# ibmpc.net
KiCad netlist of a schematic drawn in EAGLE
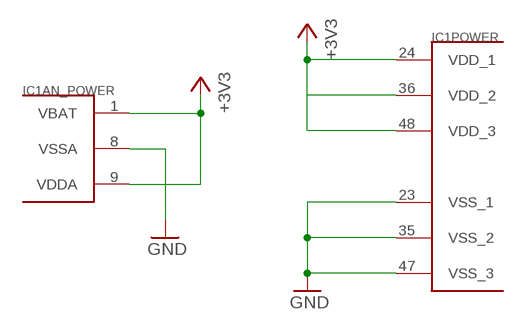
[diagram p0: schematic, sheet 1, part 1 of 2]
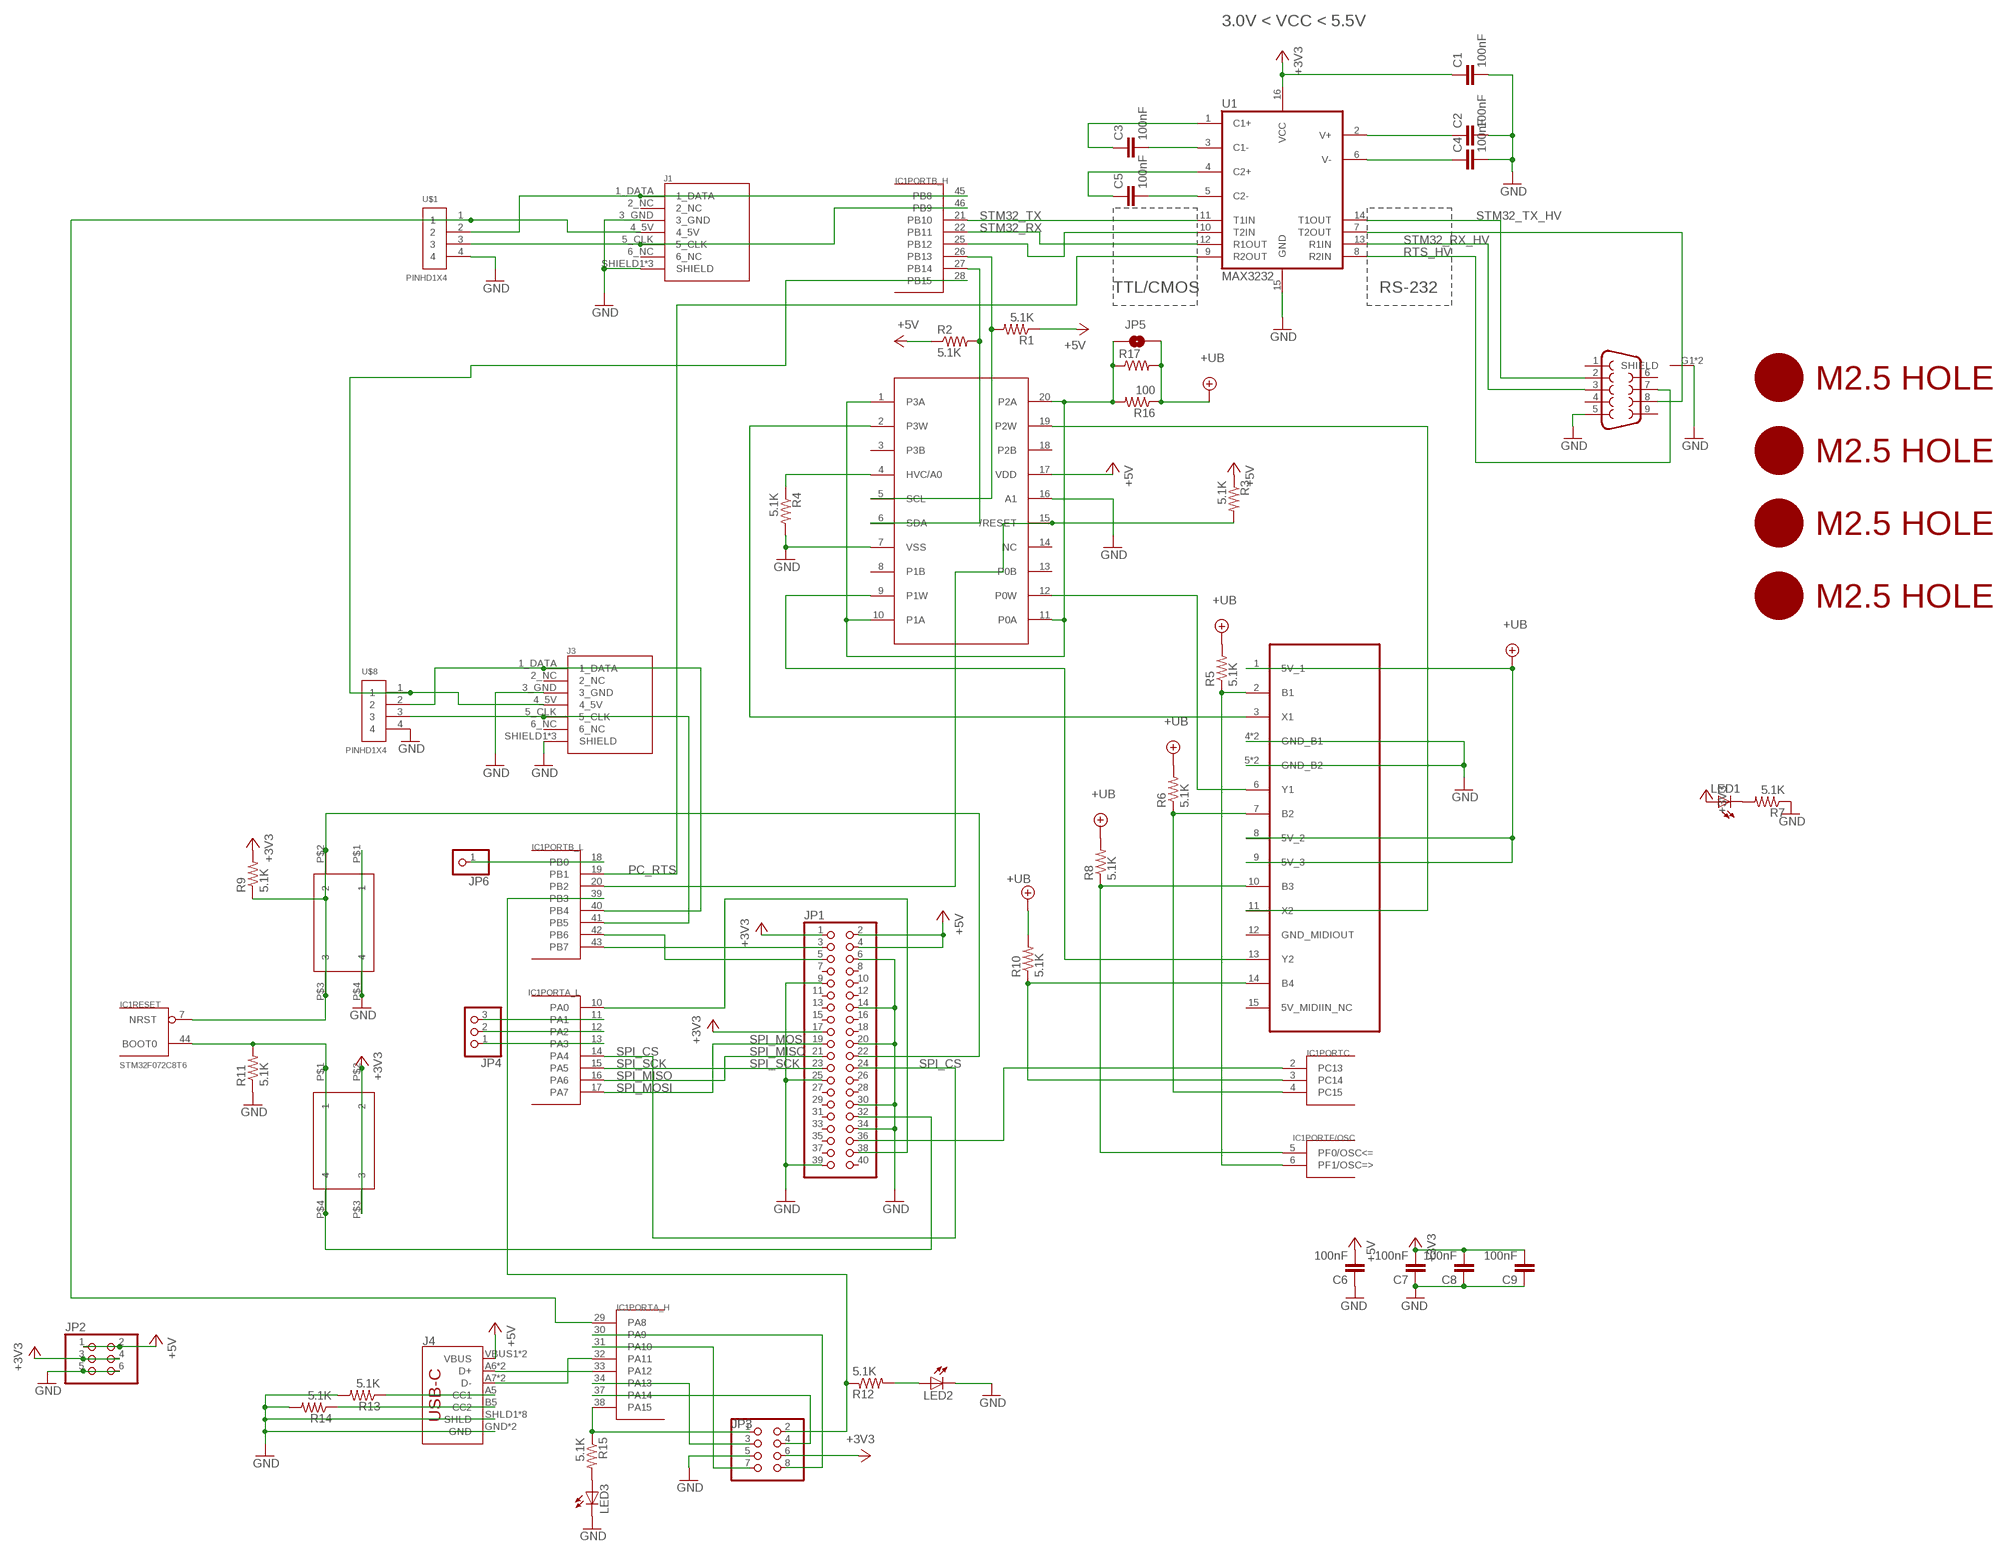
[diagram p1: schematic, sheet 1, part 2 of 2]

(export (version "E")
  (design (tool "Eeschema 10.0.6"))
  (components
    (comp (ref "C1")
      (value "100nF")
      (footprint "eagle-import:0805@1")
      (libsource (lib "eagle-import") (part "CAP0805"))
    )
    (comp (ref "C2")
      (value "100nF")
      (footprint "eagle-import:0805@1")
      (libsource (lib "eagle-import") (part "CAP0805"))
    )
    (comp (ref "C3")
      (value "100nF")
      (footprint "eagle-import:0805@1")
      (libsource (lib "eagle-import") (part "CAP0805"))
    )
    (comp (ref "C4")
      (value "100nF")
      (footprint "eagle-import:0805@1")
      (libsource (lib "eagle-import") (part "CAP0805"))
    )
    (comp (ref "C5")
      (value "100nF")
      (footprint "eagle-import:0805@1")
      (libsource (lib "eagle-import") (part "CAP0805"))
    )
    (comp (ref "C6")
      (value "100nF")
      (footprint "eagle-import:0805@1")
      (libsource (lib "eagle-import") (part "CAP0805"))
    )
    (comp (ref "C7")
      (value "100nF")
      (footprint "eagle-import:0805@1")
      (libsource (lib "eagle-import") (part "CAP0805"))
    )
    (comp (ref "C8")
      (value "100nF")
      (footprint "eagle-import:0805@1")
      (libsource (lib "eagle-import") (part "CAP0805"))
    )
    (comp (ref "C9")
      (value "100nF")
      (footprint "eagle-import:0805@1")
      (libsource (lib "eagle-import") (part "CAP0805"))
    )
    (comp (ref "IC1")
      (value "STM32F072C8T6")
      (footprint "eagle-import:TQFP48")
      (libsource (lib "eagle-import") (part "STM32F072C8T6"))
    )
    (comp (ref "J1")
      (value "DIN7")
      (footprint "eagle-import:DIN7")
      (libsource (lib "eagle-import") (part "DIN7"))
    )
    (comp (ref "J2")
      (value "DB9MALE")
      (footprint "eagle-import:DB9_MALE")
      (libsource (lib "eagle-import") (part "DB9MALE"))
    )
    (comp (ref "J3")
      (value "DIN7")
      (footprint "eagle-import:DIN7")
      (libsource (lib "eagle-import") (part "DIN7"))
    )
    (comp (ref "J4")
      (value "USB_C16PIN")
      (footprint "eagle-import:USB-C-16P")
      (libsource (lib "eagle-import") (part "USB_C16PIN"))
    )
    (comp (ref "JP1")
      (value "PINHD-2X20-BIG")
      (footprint "eagle-import:2X20-BIG")
      (libsource (lib "eagle-import") (part "PINHD-2X20-BIG"))
    )
    (comp (ref "JP2")
      (value "PINHD-2X3")
      (footprint "eagle-import:2X03")
      (libsource (lib "eagle-import") (part "PINHD-2X3"))
    )
    (comp (ref "JP3")
      (value "PINHD-2X4")
      (footprint "eagle-import:2X04")
      (libsource (lib "eagle-import") (part "PINHD-2X4"))
    )
    (comp (ref "JP4")
      (value "PINHD-1X3CB")
      (footprint "eagle-import:1X03-CLEANBIG")
      (libsource (lib "eagle-import") (part "PINHD-1X3CB"))
    )
    (comp (ref "JP5")
      (value "JUMPER-SMT_2_NO_NO-SILK")
      (footprint "eagle-import:SMT-JUMPER_2_NO_NO-SILK")
      (libsource (lib "eagle-import") (part "JUMPER-SMT_2_NO_NO-SILK"))
    )
    (comp (ref "JP6")
      (value "PINHD-1X1CB")
      (footprint "eagle-import:1X01-CLEANBIG")
      (libsource (lib "eagle-import") (part "PINHD-1X1CB"))
    )
    (comp (ref "LED1")
      (value "LEDCHIP-LED0805")
      (footprint "eagle-import:CHIP-LED0805")
      (libsource (lib "eagle-import") (part "LEDCHIP-LED0805"))
    )
    (comp (ref "LED2")
      (value "LEDCHIP-LED0805")
      (footprint "eagle-import:CHIP-LED0805")
      (libsource (lib "eagle-import") (part "LEDCHIP-LED0805"))
    )
    (comp (ref "LED3")
      (value "LEDCHIP-LED0805")
      (footprint "eagle-import:CHIP-LED0805")
      (libsource (lib "eagle-import") (part "LEDCHIP-LED0805"))
    )
    (comp (ref "R1")
      (value "5.1K")
      (footprint "eagle-import:0805")
      (libsource (lib "eagle-import") (part "RESISTOR0805-RES"))
    )
    (comp (ref "R2")
      (value "5.1K")
      (footprint "eagle-import:0805")
      (libsource (lib "eagle-import") (part "RESISTOR0805-RES"))
    )
    (comp (ref "R3")
      (value "5.1K")
      (footprint "eagle-import:0805")
      (libsource (lib "eagle-import") (part "RESISTOR0805-RES"))
    )
    (comp (ref "R4")
      (value "5.1K")
      (footprint "eagle-import:0805")
      (libsource (lib "eagle-import") (part "RESISTOR0805-RES"))
    )
    (comp (ref "R5")
      (value "5.1K")
      (footprint "eagle-import:0805")
      (libsource (lib "eagle-import") (part "RESISTOR0805-RES"))
    )
    (comp (ref "R6")
      (value "5.1K")
      (footprint "eagle-import:0805")
      (libsource (lib "eagle-import") (part "RESISTOR0805-RES"))
    )
    (comp (ref "R7")
      (value "5.1K")
      (footprint "eagle-import:0805")
      (libsource (lib "eagle-import") (part "RESISTOR0805-RES"))
    )
    (comp (ref "R8")
      (value "5.1K")
      (footprint "eagle-import:0805")
      (libsource (lib "eagle-import") (part "RESISTOR0805-RES"))
    )
    (comp (ref "R9")
      (value "5.1K")
      (footprint "eagle-import:0805")
      (libsource (lib "eagle-import") (part "RESISTOR0805-RES"))
    )
    (comp (ref "R10")
      (value "5.1K")
      (footprint "eagle-import:0805")
      (libsource (lib "eagle-import") (part "RESISTOR0805-RES"))
    )
    (comp (ref "R11")
      (value "5.1K")
      (footprint "eagle-import:0805")
      (libsource (lib "eagle-import") (part "RESISTOR0805-RES"))
    )
    (comp (ref "R12")
      (value "5.1K")
      (footprint "eagle-import:0805")
      (libsource (lib "eagle-import") (part "RESISTOR0805-RES"))
    )
    (comp (ref "R13")
      (value "5.1K")
      (footprint "eagle-import:0805")
      (libsource (lib "eagle-import") (part "RESISTOR0805-RES"))
    )
    (comp (ref "R14")
      (value "5.1K")
      (footprint "eagle-import:0805")
      (libsource (lib "eagle-import") (part "RESISTOR0805-RES"))
    )
    (comp (ref "R15")
      (value "5.1K")
      (footprint "eagle-import:0805")
      (libsource (lib "eagle-import") (part "RESISTOR0805-RES"))
    )
    (comp (ref "R16")
      (value "100")
      (footprint "eagle-import:0805")
      (libsource (lib "eagle-import") (part "RESISTOR0805-RES"))
    )
    (comp (ref "R17")
      (value "R-US_0204/7")
      (footprint "eagle-import:0204_7")
      (libsource (lib "eagle-import") (part "R-US_0204/7"))
    )
    (comp (ref "SW1")
      (value "324_SW")
      (footprint "eagle-import:342_SWICH_FOOT")
      (libsource (lib "eagle-import") (part "324_SW"))
    )
    (comp (ref "SW2")
      (value "324_SW")
      (footprint "eagle-import:342_SWICH_FOOT")
      (libsource (lib "eagle-import") (part "324_SW"))
    )
    (comp (ref "U$1")
      (value "PINHD1X4")
      (footprint "eagle-import:1X04-CLEANBIG")
      (libsource (lib "eagle-import") (part "PINHD1X4"))
    )
    (comp (ref "U$2")
      (value "M2.5HOLE")
      (footprint "eagle-import:M2.5HOLE")
      (libsource (lib "eagle-import") (part "M2.5HOLE"))
    )
    (comp (ref "U$3")
      (value "M2.5HOLE")
      (footprint "eagle-import:M2.5HOLE")
      (libsource (lib "eagle-import") (part "M2.5HOLE"))
    )
    (comp (ref "U$5")
      (value "MCP4451")
      (footprint "eagle-import:TSSOP20")
      (libsource (lib "eagle-import") (part "MCP4451"))
    )
    (comp (ref "U$6")
      (value "M2.5HOLE")
      (footprint "eagle-import:M2.5HOLE")
      (libsource (lib "eagle-import") (part "M2.5HOLE"))
    )
    (comp (ref "U$7")
      (value "M2.5HOLE")
      (footprint "eagle-import:M2.5HOLE")
      (libsource (lib "eagle-import") (part "M2.5HOLE"))
    )
    (comp (ref "U$8")
      (value "PINHD1X4")
      (footprint "eagle-import:1X04-CLEANBIG")
      (libsource (lib "eagle-import") (part "PINHD1X4"))
    )
    (comp (ref "U$9")
      (value "GAMEPORT_15P")
      (footprint "eagle-import:DA15")
      (libsource (lib "eagle-import") (part "GAMEPORT_15P"))
    )
    (comp (ref "U1")
      (value "MAX3232")
      (footprint "eagle-import:SO016")
      (libsource (lib "eagle-import") (part "MAX232SOIC16"))
    )
  )
  (nets
    (net (code "1") (name "+3V3") (class "Default")
      (node (ref "C1") (pin "1") (pinfunction "1_1") (pintype "passive"))
      (node (ref "C7") (pin "2") (pinfunction "2_2") (pintype "passive"))
      (node (ref "C8") (pin "2") (pinfunction "2_2") (pintype "passive"))
      (node (ref "C9") (pin "2") (pinfunction "2_2") (pintype "passive"))
      (node (ref "IC1") (pin "1") (pinfunction "VBAT_1") (pintype "power_in"))
      (node (ref "IC1") (pin "24") (pinfunction "VDD_1_24") (pintype "power_in"))
      (node (ref "IC1") (pin "36") (pinfunction "VDD_2_36") (pintype "power_in"))
      (node (ref "IC1") (pin "48") (pinfunction "VDD_3_48") (pintype "power_in"))
      (node (ref "IC1") (pin "9") (pinfunction "VDDA_9") (pintype "power_in"))
      (node (ref "JP1") (pin "1") (pinfunction "1_1") (pintype "passive"))
      (node (ref "JP1") (pin "17") (pinfunction "17_17") (pintype "passive"))
      (node (ref "JP2") (pin "3") (pinfunction "3_3") (pintype "passive"))
      (node (ref "JP2") (pin "4") (pinfunction "4_4") (pintype "passive"))
      (node (ref "JP3") (pin "6") (pinfunction "6_6") (pintype "passive"))
      (node (ref "LED1") (pin "A") (pinfunction "A_A") (pintype "passive"))
      (node (ref "R9") (pin "2") (pinfunction "2_2") (pintype "passive"))
      (node (ref "SW2") (pin "P$2") (pinfunction "2_P$2") (pintype "bidirectional"))
      (node (ref "SW2") (pin "P$3") (pinfunction "3_P$3") (pintype "bidirectional"))
      (node (ref "U1") (pin "16") (pinfunction "VCC_16") (pintype "bidirectional"))
    )
    (net (code "2") (name "+5V") (class "Default")
      (node (ref "C6") (pin "2") (pinfunction "2_2") (pintype "passive"))
      (node (ref "J4") (pin "VBUS1") (pinfunction "VBUS_VBUS1") (pintype "bidirectional"))
      (node (ref "J4") (pin "VBUS2") (pinfunction "VBUS_VBUS2") (pintype "bidirectional"))
      (node (ref "JP1") (pin "2") (pinfunction "2_2") (pintype "passive"))
      (node (ref "JP1") (pin "4") (pinfunction "4_4") (pintype "passive"))
      (node (ref "JP2") (pin "1") (pinfunction "1_1") (pintype "passive"))
      (node (ref "JP2") (pin "2") (pinfunction "2_2") (pintype "passive"))
      (node (ref "R1") (pin "1") (pinfunction "1_1") (pintype "passive"))
      (node (ref "R2") (pin "1") (pinfunction "1_1") (pintype "passive"))
      (node (ref "R3") (pin "1") (pinfunction "1_1") (pintype "passive"))
      (node (ref "U$5") (pin "17") (pinfunction "VDD_17") (pintype "bidirectional"))
    )
    (net (code "3") (name "+UB") (class "Default")
      (node (ref "JP5") (pin "2") (pinfunction "2_2") (pintype "passive"))
      (node (ref "R10") (pin "2") (pinfunction "2_2") (pintype "passive"))
      (node (ref "R16") (pin "1") (pinfunction "1_1") (pintype "passive"))
      (node (ref "R17") (pin "2") (pinfunction "2_2") (pintype "passive"))
      (node (ref "R5") (pin "2") (pinfunction "2_2") (pintype "passive"))
      (node (ref "R6") (pin "2") (pinfunction "2_2") (pintype "passive"))
      (node (ref "R8") (pin "2") (pinfunction "2_2") (pintype "passive"))
      (node (ref "U$9") (pin "1") (pinfunction "5V_1_1") (pintype "bidirectional"))
      (node (ref "U$9") (pin "8") (pinfunction "5V_2_8") (pintype "bidirectional"))
      (node (ref "U$9") (pin "9") (pinfunction "5V_3_9") (pintype "bidirectional"))
    )
    (net (code "4") (name "/PC_RTS") (class "Default")
      (node (ref "IC1") (pin "19") (pinfunction "PB1_19") (pintype "bidirectional"))
      (node (ref "U1") (pin "9") (pinfunction "R2OUT_9") (pintype "output"))
    )
    (net (code "5") (name "/RTS_HV") (class "Default")
      (node (ref "J2") (pin "7") (pinfunction "7_7") (pintype "passive"))
      (node (ref "U1") (pin "8") (pinfunction "R2IN_8") (pintype "input"))
    )
    (net (code "6") (name "/SPI_CS") (class "Default")
      (node (ref "IC1") (pin "14") (pinfunction "PA4_14") (pintype "bidirectional"))
      (node (ref "JP1") (pin "24") (pinfunction "24_24") (pintype "passive"))
    )
    (net (code "7") (name "/SPI_MISO") (class "Default")
      (node (ref "IC1") (pin "16") (pinfunction "PA6_16") (pintype "bidirectional"))
      (node (ref "JP1") (pin "21") (pinfunction "21_21") (pintype "passive"))
    )
    (net (code "8") (name "/SPI_MOSI") (class "Default")
      (node (ref "IC1") (pin "17") (pinfunction "PA7_17") (pintype "bidirectional"))
      (node (ref "JP1") (pin "19") (pinfunction "19_19") (pintype "passive"))
    )
    (net (code "9") (name "/SPI_SCK") (class "Default")
      (node (ref "IC1") (pin "15") (pinfunction "PA5_15") (pintype "bidirectional"))
      (node (ref "JP1") (pin "23") (pinfunction "23_23") (pintype "passive"))
    )
    (net (code "10") (name "/STM32_RX") (class "Default")
      (node (ref "IC1") (pin "22") (pinfunction "PB11_22") (pintype "bidirectional"))
      (node (ref "U1") (pin "12") (pinfunction "R1OUT_12") (pintype "output"))
    )
    (net (code "11") (name "/STM32_RX_HV") (class "Default")
      (node (ref "J2") (pin "3") (pinfunction "3_3") (pintype "passive"))
      (node (ref "U1") (pin "13") (pinfunction "R1IN_13") (pintype "input"))
    )
    (net (code "12") (name "/STM32_TX") (class "Default")
      (node (ref "IC1") (pin "21") (pinfunction "PB10_21") (pintype "bidirectional"))
      (node (ref "U1") (pin "11") (pinfunction "T1IN_11") (pintype "input"))
    )
    (net (code "13") (name "/STM32_TX_HV") (class "Default")
      (node (ref "J2") (pin "2") (pinfunction "2_2") (pintype "passive"))
      (node (ref "U1") (pin "14") (pinfunction "T1OUT_14") (pintype "output"))
    )
    (net (code "14") (name "GND") (class "Default")
      (node (ref "C1") (pin "2") (pinfunction "2_2") (pintype "passive"))
      (node (ref "C2") (pin "2") (pinfunction "2_2") (pintype "passive"))
      (node (ref "C4") (pin "2") (pinfunction "2_2") (pintype "passive"))
      (node (ref "C6") (pin "1") (pinfunction "1_1") (pintype "passive"))
      (node (ref "C7") (pin "1") (pinfunction "1_1") (pintype "passive"))
      (node (ref "C8") (pin "1") (pinfunction "1_1") (pintype "passive"))
      (node (ref "C9") (pin "1") (pinfunction "1_1") (pintype "passive"))
      (node (ref "IC1") (pin "23") (pinfunction "VSS_1_23") (pintype "power_in"))
      (node (ref "IC1") (pin "35") (pinfunction "VSS_2_35") (pintype "power_in"))
      (node (ref "IC1") (pin "47") (pinfunction "VSS_3_47") (pintype "power_in"))
      (node (ref "IC1") (pin "8") (pinfunction "VSSA_8") (pintype "power_in"))
      (node (ref "J1") (pin "3_GND") (pinfunction "3_GND_3_GND") (pintype "bidirectional"))
      (node (ref "J1") (pin "SHIELD1") (pinfunction "SHIELD_SHIELD1") (pintype "bidirectional"))
      (node (ref "J1") (pin "SHIELD2") (pinfunction "SHIELD_SHIELD2") (pintype "bidirectional"))
      (node (ref "J1") (pin "SHIELD3") (pinfunction "SHIELD_SHIELD3") (pintype "bidirectional"))
      (node (ref "J2") (pin "5") (pinfunction "5_5") (pintype "passive"))
      (node (ref "J2") (pin "G1") (pinfunction "SHIELD_G1") (pintype "bidirectional"))
      (node (ref "J2") (pin "G2") (pinfunction "SHIELD_G2") (pintype "bidirectional"))
      (node (ref "J3") (pin "3_GND") (pinfunction "3_GND_3_GND") (pintype "bidirectional"))
      (node (ref "J3") (pin "SHIELD1") (pinfunction "SHIELD_SHIELD1") (pintype "bidirectional"))
      (node (ref "J3") (pin "SHIELD2") (pinfunction "SHIELD_SHIELD2") (pintype "bidirectional"))
      (node (ref "J3") (pin "SHIELD3") (pinfunction "SHIELD_SHIELD3") (pintype "bidirectional"))
      (node (ref "J4") (pin "GND") (pinfunction "GND_GND") (pintype "bidirectional"))
      (node (ref "J4") (pin "GND2") (pinfunction "GND_GND2") (pintype "bidirectional"))
      (node (ref "J4") (pin "SHLD1") (pinfunction "SHLD_SHLD1") (pintype "bidirectional"))
      (node (ref "J4") (pin "SHLD2") (pinfunction "SHLD_SHLD2") (pintype "bidirectional"))
      (node (ref "J4") (pin "SHLD3") (pinfunction "SHLD_SHLD3") (pintype "bidirectional"))
      (node (ref "J4") (pin "SHLD4") (pinfunction "SHLD_SHLD4") (pintype "bidirectional"))
      (node (ref "J4") (pin "SHLD5") (pinfunction "SHLD_SHLD5") (pintype "bidirectional"))
      (node (ref "J4") (pin "SHLD6") (pinfunction "SHLD_SHLD6") (pintype "bidirectional"))
      (node (ref "J4") (pin "SHLD7") (pinfunction "SHLD_SHLD7") (pintype "bidirectional"))
      (node (ref "J4") (pin "SHLD8") (pinfunction "SHLD_SHLD8") (pintype "bidirectional"))
      (node (ref "JP1") (pin "14") (pinfunction "14_14") (pintype "passive"))
      (node (ref "JP1") (pin "20") (pinfunction "20_20") (pintype "passive"))
      (node (ref "JP1") (pin "25") (pinfunction "25_25") (pintype "passive"))
      (node (ref "JP1") (pin "30") (pinfunction "30_30") (pintype "passive"))
      (node (ref "JP1") (pin "34") (pinfunction "34_34") (pintype "passive"))
      (node (ref "JP1") (pin "39") (pinfunction "39_39") (pintype "passive"))
      (node (ref "JP1") (pin "6") (pinfunction "6_6") (pintype "passive"))
      (node (ref "JP1") (pin "9") (pinfunction "9_9") (pintype "passive"))
      (node (ref "JP2") (pin "5") (pinfunction "5_5") (pintype "passive"))
      (node (ref "JP2") (pin "6") (pinfunction "6_6") (pintype "passive"))
      (node (ref "JP3") (pin "5") (pinfunction "5_5") (pintype "passive"))
      (node (ref "LED2") (pin "C") (pinfunction "C_C") (pintype "passive"))
      (node (ref "LED3") (pin "C") (pinfunction "C_C") (pintype "passive"))
      (node (ref "R11") (pin "1") (pinfunction "1_1") (pintype "passive"))
      (node (ref "R13") (pin "2") (pinfunction "2_2") (pintype "passive"))
      (node (ref "R14") (pin "2") (pinfunction "2_2") (pintype "passive"))
      (node (ref "R4") (pin "2") (pinfunction "2_2") (pintype "passive"))
      (node (ref "R7") (pin "1") (pinfunction "1_1") (pintype "passive"))
      (node (ref "SW1") (pin "P$1") (pinfunction "1_P$1") (pintype "bidirectional"))
      (node (ref "SW1") (pin "P$4") (pinfunction "4_P$4") (pintype "bidirectional"))
      (node (ref "U$1") (pin "4") (pinfunction "4_4") (pintype "bidirectional"))
      (node (ref "U$5") (pin "16") (pinfunction "A1_16") (pintype "bidirectional"))
      (node (ref "U$5") (pin "7") (pinfunction "VSS_7") (pintype "bidirectional"))
      (node (ref "U$8") (pin "4") (pinfunction "4_4") (pintype "bidirectional"))
      (node (ref "U$9") (pin "4") (pinfunction "GND_B1_4") (pintype "bidirectional"))
      (node (ref "U$9") (pin "5") (pinfunction "GND_B2_5") (pintype "bidirectional"))
      (node (ref "U$9") (pin "G1") (pinfunction "GND_B1_G1") (pintype "bidirectional"))
      (node (ref "U$9") (pin "G2") (pinfunction "GND_B2_G2") (pintype "bidirectional"))
      (node (ref "U1") (pin "15") (pinfunction "GND_15") (pintype "bidirectional"))
    )
    (net (code "15") (name "Net-(IC1B-PA8)") (class "Default")
      (node (ref "IC1") (pin "29") (pinfunction "PA8_29") (pintype "bidirectional"))
      (node (ref "J1") (pin "4_5V") (pinfunction "4_5V_4_5V") (pintype "bidirectional"))
      (node (ref "U$1") (pin "1") (pinfunction "1_1") (pintype "bidirectional"))
    )
    (net (code "16") (name "Net-(IC1B-PA9)") (class "Default")
      (node (ref "IC1") (pin "30") (pinfunction "PA9_30") (pintype "bidirectional"))
      (node (ref "JP3") (pin "8") (pinfunction "8_8") (pintype "passive"))
    )
    (net (code "17") (name "Net-(IC1B-PA10)") (class "Default")
      (node (ref "IC1") (pin "31") (pinfunction "PA10_31") (pintype "bidirectional"))
      (node (ref "JP3") (pin "7") (pinfunction "7_7") (pintype "passive"))
    )
    (net (code "18") (name "Net-(IC1B-PA11)") (class "Default")
      (node (ref "IC1") (pin "32") (pinfunction "PA11_32") (pintype "bidirectional"))
      (node (ref "J4") (pin "A7") (pinfunction "D-_A7") (pintype "bidirectional"))
      (node (ref "J4") (pin "B7") (pinfunction "D-_B7") (pintype "bidirectional"))
    )
    (net (code "19") (name "Net-(IC1B-PA12)") (class "Default")
      (node (ref "IC1") (pin "33") (pinfunction "PA12_33") (pintype "bidirectional"))
      (node (ref "J4") (pin "A6") (pinfunction "D+_A6") (pintype "bidirectional"))
      (node (ref "J4") (pin "B6") (pinfunction "D+_B6") (pintype "bidirectional"))
    )
    (net (code "20") (name "Net-(IC1B-PA13)") (class "Default")
      (node (ref "IC1") (pin "34") (pinfunction "PA13_34") (pintype "bidirectional"))
      (node (ref "JP3") (pin "3") (pinfunction "3_3") (pintype "passive"))
    )
    (net (code "21") (name "Net-(IC1B-PA14)") (class "Default")
      (node (ref "IC1") (pin "37") (pinfunction "PA14_37") (pintype "bidirectional"))
      (node (ref "JP3") (pin "4") (pinfunction "4_4") (pintype "passive"))
    )
    (net (code "22") (name "Net-(IC1B-PA15)") (class "Default")
      (node (ref "IC1") (pin "38") (pinfunction "PA15_38") (pintype "bidirectional"))
      (node (ref "JP3") (pin "1") (pinfunction "1_1") (pintype "passive"))
      (node (ref "R15") (pin "1") (pinfunction "1_1") (pintype "passive"))
    )
    (net (code "23") (name "Net-(IC1C-PA0)") (class "Default")
      (node (ref "IC1") (pin "10") (pinfunction "PA0_10") (pintype "bidirectional"))
      (node (ref "JP1") (pin "38") (pinfunction "38_38") (pintype "passive"))
    )
    (net (code "24") (name "Net-(IC1C-PA1)") (class "Default")
      (node (ref "IC1") (pin "11") (pinfunction "PA1_11") (pintype "bidirectional"))
      (node (ref "JP4") (pin "3") (pinfunction "3_3") (pintype "passive"))
    )
    (net (code "25") (name "Net-(IC1C-PA2)") (class "Default")
      (node (ref "IC1") (pin "12") (pinfunction "PA2_12") (pintype "bidirectional"))
      (node (ref "JP4") (pin "2") (pinfunction "2_2") (pintype "passive"))
    )
    (net (code "26") (name "Net-(IC1C-PA3)") (class "Default")
      (node (ref "IC1") (pin "13") (pinfunction "PA3_13") (pintype "bidirectional"))
      (node (ref "JP4") (pin "1") (pinfunction "1_1") (pintype "passive"))
    )
    (net (code "27") (name "Net-(IC1D-PB8)") (class "Default")
      (node (ref "IC1") (pin "45") (pinfunction "PB8_45") (pintype "bidirectional"))
      (node (ref "J1") (pin "1_DATA") (pinfunction "1_DATA_1_DATA") (pintype "bidirectional"))
      (node (ref "U$1") (pin "2") (pinfunction "2_2") (pintype "bidirectional"))
    )
    (net (code "28") (name "Net-(IC1D-PB9)") (class "Default")
      (node (ref "IC1") (pin "46") (pinfunction "PB9_46") (pintype "bidirectional"))
      (node (ref "J1") (pin "5_CLK") (pinfunction "5_CLK_5_CLK") (pintype "bidirectional"))
      (node (ref "U$1") (pin "3") (pinfunction "3_3") (pintype "bidirectional"))
    )
    (net (code "29") (name "Net-(IC1D-PB12)") (class "Default")
      (node (ref "IC1") (pin "25") (pinfunction "PB12_25") (pintype "bidirectional"))
      (node (ref "U1") (pin "10") (pinfunction "T2IN_10") (pintype "input"))
    )
    (net (code "30") (name "Net-(IC1D-PB13)") (class "Default")
      (node (ref "IC1") (pin "26") (pinfunction "PB13_26") (pintype "bidirectional"))
      (node (ref "R1") (pin "2") (pinfunction "2_2") (pintype "passive"))
      (node (ref "U$5") (pin "5") (pinfunction "SCL_5") (pintype "bidirectional"))
    )
    (net (code "31") (name "Net-(IC1D-PB14)") (class "Default")
      (node (ref "IC1") (pin "27") (pinfunction "PB14_27") (pintype "bidirectional"))
      (node (ref "R2") (pin "2") (pinfunction "2_2") (pintype "passive"))
      (node (ref "U$5") (pin "6") (pinfunction "SDA_6") (pintype "bidirectional"))
    )
    (net (code "32") (name "Net-(IC1D-PB15)") (class "Default")
      (node (ref "IC1") (pin "28") (pinfunction "PB15_28") (pintype "bidirectional"))
      (node (ref "J3") (pin "4_5V") (pinfunction "4_5V_4_5V") (pintype "bidirectional"))
      (node (ref "U$8") (pin "1") (pinfunction "1_1") (pintype "bidirectional"))
    )
    (net (code "33") (name "Net-(IC1E-PB0)") (class "Default")
      (node (ref "IC1") (pin "18") (pinfunction "PB0_18") (pintype "bidirectional"))
      (node (ref "JP6") (pin "1") (pinfunction "1_1") (pintype "passive"))
    )
    (net (code "34") (name "Net-(IC1E-PB2)") (class "Default")
      (node (ref "IC1") (pin "20") (pinfunction "PB2_20") (pintype "bidirectional"))
      (node (ref "R3") (pin "2") (pinfunction "2_2") (pintype "passive"))
      (node (ref "U$5") (pin "15") (pinfunction "/RESET_15") (pintype "bidirectional"))
    )
    (net (code "35") (name "Net-(IC1E-PB3)") (class "Default")
      (node (ref "IC1") (pin "39") (pinfunction "PB3_39") (pintype "bidirectional"))
      (node (ref "JP3") (pin "2") (pinfunction "2_2") (pintype "passive"))
      (node (ref "R12") (pin "1") (pinfunction "1_1") (pintype "passive"))
    )
    (net (code "36") (name "Net-(IC1E-PB4)") (class "Default")
      (node (ref "IC1") (pin "40") (pinfunction "PB4_40") (pintype "bidirectional"))
      (node (ref "J3") (pin "1_DATA") (pinfunction "1_DATA_1_DATA") (pintype "bidirectional"))
      (node (ref "U$8") (pin "2") (pinfunction "2_2") (pintype "bidirectional"))
    )
    (net (code "37") (name "Net-(IC1E-PB5)") (class "Default")
      (node (ref "IC1") (pin "41") (pinfunction "PB5_41") (pintype "bidirectional"))
      (node (ref "J3") (pin "5_CLK") (pinfunction "5_CLK_5_CLK") (pintype "bidirectional"))
      (node (ref "U$8") (pin "3") (pinfunction "3_3") (pintype "bidirectional"))
    )
    (net (code "38") (name "Net-(IC1E-PB6)") (class "Default")
      (node (ref "IC1") (pin "42") (pinfunction "PB6_42") (pintype "bidirectional"))
      (node (ref "JP1") (pin "5") (pinfunction "5_5") (pintype "passive"))
    )
    (net (code "39") (name "Net-(IC1E-PB7)") (class "Default")
      (node (ref "IC1") (pin "43") (pinfunction "PB7_43") (pintype "bidirectional"))
      (node (ref "JP1") (pin "3") (pinfunction "3_3") (pintype "passive"))
    )
    (net (code "40") (name "Net-(IC1F-PC13)") (class "Default")
      (node (ref "IC1") (pin "2") (pinfunction "PC13_2") (pintype "bidirectional"))
      (node (ref "JP1") (pin "36") (pinfunction "36_36") (pintype "passive"))
    )
    (net (code "41") (name "Net-(IC1F-PC14)") (class "Default")
      (node (ref "IC1") (pin "3") (pinfunction "PC14_3") (pintype "bidirectional"))
      (node (ref "R10") (pin "1") (pinfunction "1_1") (pintype "passive"))
      (node (ref "U$9") (pin "14") (pinfunction "B4_14") (pintype "bidirectional"))
    )
    (net (code "42") (name "Net-(IC1F-PC15)") (class "Default")
      (node (ref "IC1") (pin "4") (pinfunction "PC15_4") (pintype "bidirectional"))
      (node (ref "R6") (pin "1") (pinfunction "1_1") (pintype "passive"))
      (node (ref "U$9") (pin "7") (pinfunction "B2_7") (pintype "bidirectional"))
    )
    (net (code "43") (name "Net-(IC1G-PF0{slash}OSC<=)") (class "Default")
      (node (ref "IC1") (pin "5") (pinfunction "PF0/OSC<=_5") (pintype "bidirectional"))
      (node (ref "R8") (pin "1") (pinfunction "1_1") (pintype "passive"))
      (node (ref "U$9") (pin "10") (pinfunction "B3_10") (pintype "bidirectional"))
    )
    (net (code "44") (name "Net-(IC1G-PF1{slash}OSC=>)") (class "Default")
      (node (ref "IC1") (pin "6") (pinfunction "PF1/OSC=>_6") (pintype "bidirectional"))
      (node (ref "R5") (pin "1") (pinfunction "1_1") (pintype "passive"))
      (node (ref "U$9") (pin "2") (pinfunction "B1_2") (pintype "bidirectional"))
    )
    (net (code "45") (name "Net-(IC1I-BOOT0)") (class "Default")
      (node (ref "IC1") (pin "44") (pinfunction "BOOT0_44") (pintype "input"))
      (node (ref "JP1") (pin "32") (pinfunction "32_32") (pintype "passive"))
      (node (ref "R11") (pin "2") (pinfunction "2_2") (pintype "passive"))
      (node (ref "SW2") (pin "P$1") (pinfunction "1_P$1") (pintype "bidirectional"))
      (node (ref "SW2") (pin "P$4") (pinfunction "4_P$4") (pintype "bidirectional"))
    )
    (net (code "46") (name "Net-(IC1I-NRST)") (class "Default")
      (node (ref "IC1") (pin "7") (pinfunction "NRST_7") (pintype "input"))
      (node (ref "JP1") (pin "22") (pinfunction "22_22") (pintype "passive"))
      (node (ref "R9") (pin "1") (pinfunction "1_1") (pintype "passive"))
      (node (ref "SW1") (pin "P$2") (pinfunction "2_P$2") (pintype "bidirectional"))
      (node (ref "SW1") (pin "P$3") (pinfunction "3_P$3") (pintype "bidirectional"))
    )
    (net (code "47") (name "Net-(J4-CC1)") (class "Default")
      (node (ref "J4") (pin "A5") (pinfunction "CC1_A5") (pintype "bidirectional"))
      (node (ref "R13") (pin "1") (pinfunction "1_1") (pintype "passive"))
    )
    (net (code "48") (name "Net-(J4-CC2)") (class "Default")
      (node (ref "J4") (pin "B5") (pinfunction "CC2_B5") (pintype "bidirectional"))
      (node (ref "R14") (pin "1") (pinfunction "1_1") (pintype "passive"))
    )
    (net (code "49") (name "Net-(LED1-PadC)") (class "Default")
      (node (ref "LED1") (pin "C") (pinfunction "C_C") (pintype "passive"))
      (node (ref "R7") (pin "2") (pinfunction "2_2") (pintype "passive"))
    )
    (net (code "50") (name "Net-(LED2-PadA)") (class "Default")
      (node (ref "LED2") (pin "A") (pinfunction "A_A") (pintype "passive"))
      (node (ref "R12") (pin "2") (pinfunction "2_2") (pintype "passive"))
    )
    (net (code "51") (name "Net-(LED3-PadA)") (class "Default")
      (node (ref "LED3") (pin "A") (pinfunction "A_A") (pintype "passive"))
      (node (ref "R15") (pin "2") (pinfunction "2_2") (pintype "passive"))
    )
    (net (code "52") (name "Net-(U$5-HVC{slash}A0)") (class "Default")
      (node (ref "R4") (pin "1") (pinfunction "1_1") (pintype "passive"))
      (node (ref "U$5") (pin "4") (pinfunction "HVC/A0_4") (pintype "bidirectional"))
    )
    (net (code "53") (name "Net-(U$5-P0A)") (class "Default")
      (node (ref "JP5") (pin "1") (pinfunction "1_1") (pintype "passive"))
      (node (ref "R16") (pin "2") (pinfunction "2_2") (pintype "passive"))
      (node (ref "R17") (pin "1") (pinfunction "1_1") (pintype "passive"))
      (node (ref "U$5") (pin "1") (pinfunction "P3A_1") (pintype "bidirectional"))
      (node (ref "U$5") (pin "10") (pinfunction "P1A_10") (pintype "bidirectional"))
      (node (ref "U$5") (pin "11") (pinfunction "P0A_11") (pintype "bidirectional"))
      (node (ref "U$5") (pin "20") (pinfunction "P2A_20") (pintype "bidirectional"))
    )
    (net (code "54") (name "Net-(U$5-P0W)") (class "Default")
      (node (ref "U$5") (pin "12") (pinfunction "P0W_12") (pintype "bidirectional"))
      (node (ref "U$9") (pin "6") (pinfunction "Y1_6") (pintype "bidirectional"))
    )
    (net (code "55") (name "Net-(U$5-P1W)") (class "Default")
      (node (ref "U$5") (pin "9") (pinfunction "P1W_9") (pintype "bidirectional"))
      (node (ref "U$9") (pin "13") (pinfunction "Y2_13") (pintype "bidirectional"))
    )
    (net (code "56") (name "Net-(U$5-P2W)") (class "Default")
      (node (ref "U$5") (pin "19") (pinfunction "P2W_19") (pintype "bidirectional"))
      (node (ref "U$9") (pin "11") (pinfunction "X2_11") (pintype "bidirectional"))
    )
    (net (code "57") (name "Net-(U$5-P3W)") (class "Default")
      (node (ref "U$5") (pin "2") (pinfunction "P3W_2") (pintype "bidirectional"))
      (node (ref "U$9") (pin "3") (pinfunction "X1_3") (pintype "bidirectional"))
    )
    (net (code "58") (name "Net-(U1-C1+)") (class "Default")
      (node (ref "C3") (pin "1") (pinfunction "1_1") (pintype "passive"))
      (node (ref "U1") (pin "1") (pinfunction "C1+_1") (pintype "bidirectional"))
    )
    (net (code "59") (name "Net-(U1-C1-)") (class "Default")
      (node (ref "C3") (pin "2") (pinfunction "2_2") (pintype "passive"))
      (node (ref "U1") (pin "3") (pinfunction "C1-_3") (pintype "bidirectional"))
    )
    (net (code "60") (name "Net-(U1-C2+)") (class "Default")
      (node (ref "C5") (pin "1") (pinfunction "1_1") (pintype "passive"))
      (node (ref "U1") (pin "4") (pinfunction "C2+_4") (pintype "bidirectional"))
    )
    (net (code "61") (name "Net-(U1-C2-)") (class "Default")
      (node (ref "C5") (pin "2") (pinfunction "2_2") (pintype "passive"))
      (node (ref "U1") (pin "5") (pinfunction "C2-_5") (pintype "bidirectional"))
    )
    (net (code "62") (name "Net-(U1-T2OUT)") (class "Default")
      (node (ref "J2") (pin "8") (pinfunction "8_8") (pintype "passive"))
      (node (ref "U1") (pin "7") (pinfunction "T2OUT_7") (pintype "output"))
    )
    (net (code "63") (name "Net-(U1-V+)") (class "Default")
      (node (ref "C2") (pin "1") (pinfunction "1_1") (pintype "passive"))
      (node (ref "U1") (pin "2") (pinfunction "V+_2") (pintype "bidirectional"))
    )
    (net (code "64") (name "Net-(U1-V-)") (class "Default")
      (node (ref "C4") (pin "1") (pinfunction "1_1") (pintype "passive"))
      (node (ref "U1") (pin "6") (pinfunction "V-_6") (pintype "bidirectional"))
    )
    (net (code "65") (name "unconnected-(J1-Pad2_NC)") (class "Default")
      (node (ref "J1") (pin "2_NC") (pinfunction "2_NC_2_NC") (pintype "bidirectional"))
    )
    (net (code "66") (name "unconnected-(J1-Pad6_NC)") (class "Default")
      (node (ref "J1") (pin "6_NC") (pinfunction "6_NC_6_NC") (pintype "bidirectional"))
    )
    (net (code "67") (name "unconnected-(J2-Pad1)") (class "Default")
      (node (ref "J2") (pin "1") (pinfunction "1_1") (pintype "passive"))
    )
    (net (code "68") (name "unconnected-(J2-Pad4)") (class "Default")
      (node (ref "J2") (pin "4") (pinfunction "4_4") (pintype "passive"))
    )
    (net (code "69") (name "unconnected-(J2-Pad6)") (class "Default")
      (node (ref "J2") (pin "6") (pinfunction "6_6") (pintype "passive"))
    )
    (net (code "70") (name "unconnected-(J2-Pad9)") (class "Default")
      (node (ref "J2") (pin "9") (pinfunction "9_9") (pintype "passive"))
    )
    (net (code "71") (name "unconnected-(J3-Pad2_NC)") (class "Default")
      (node (ref "J3") (pin "2_NC") (pinfunction "2_NC_2_NC") (pintype "bidirectional"))
    )
    (net (code "72") (name "unconnected-(J3-Pad6_NC)") (class "Default")
      (node (ref "J3") (pin "6_NC") (pinfunction "6_NC_6_NC") (pintype "bidirectional"))
    )
    (net (code "73") (name "unconnected-(JP1-Pad7)") (class "Default")
      (node (ref "JP1") (pin "7") (pinfunction "7_7") (pintype "passive"))
    )
    (net (code "74") (name "unconnected-(JP1-Pad8)") (class "Default")
      (node (ref "JP1") (pin "8") (pinfunction "8_8") (pintype "passive"))
    )
    (net (code "75") (name "unconnected-(JP1-Pad10)") (class "Default")
      (node (ref "JP1") (pin "10") (pinfunction "10_10") (pintype "passive"))
    )
    (net (code "76") (name "unconnected-(JP1-Pad11)") (class "Default")
      (node (ref "JP1") (pin "11") (pinfunction "11_11") (pintype "passive"))
    )
    (net (code "77") (name "unconnected-(JP1-Pad12)") (class "Default")
      (node (ref "JP1") (pin "12") (pinfunction "12_12") (pintype "passive"))
    )
    (net (code "78") (name "unconnected-(JP1-Pad13)") (class "Default")
      (node (ref "JP1") (pin "13") (pinfunction "13_13") (pintype "passive"))
    )
    (net (code "79") (name "unconnected-(JP1-Pad15)") (class "Default")
      (node (ref "JP1") (pin "15") (pinfunction "15_15") (pintype "passive"))
    )
    (net (code "80") (name "unconnected-(JP1-Pad16)") (class "Default")
      (node (ref "JP1") (pin "16") (pinfunction "16_16") (pintype "passive"))
    )
    (net (code "81") (name "unconnected-(JP1-Pad18)") (class "Default")
      (node (ref "JP1") (pin "18") (pinfunction "18_18") (pintype "passive"))
    )
    (net (code "82") (name "unconnected-(JP1-Pad26)") (class "Default")
      (node (ref "JP1") (pin "26") (pinfunction "26_26") (pintype "passive"))
    )
    (net (code "83") (name "unconnected-(JP1-Pad27)") (class "Default")
      (node (ref "JP1") (pin "27") (pinfunction "27_27") (pintype "passive"))
    )
    (net (code "84") (name "unconnected-(JP1-Pad28)") (class "Default")
      (node (ref "JP1") (pin "28") (pinfunction "28_28") (pintype "passive"))
    )
    (net (code "85") (name "unconnected-(JP1-Pad29)") (class "Default")
      (node (ref "JP1") (pin "29") (pinfunction "29_29") (pintype "passive"))
    )
    (net (code "86") (name "unconnected-(JP1-Pad31)") (class "Default")
      (node (ref "JP1") (pin "31") (pinfunction "31_31") (pintype "passive"))
    )
    (net (code "87") (name "unconnected-(JP1-Pad33)") (class "Default")
      (node (ref "JP1") (pin "33") (pinfunction "33_33") (pintype "passive"))
    )
    (net (code "88") (name "unconnected-(JP1-Pad35)") (class "Default")
      (node (ref "JP1") (pin "35") (pinfunction "35_35") (pintype "passive"))
    )
    (net (code "89") (name "unconnected-(JP1-Pad37)") (class "Default")
      (node (ref "JP1") (pin "37") (pinfunction "37_37") (pintype "passive"))
    )
    (net (code "90") (name "unconnected-(JP1-Pad40)") (class "Default")
      (node (ref "JP1") (pin "40") (pinfunction "40_40") (pintype "passive"))
    )
    (net (code "91") (name "unconnected-(U$5-NC-Pad14)") (class "Default")
      (node (ref "U$5") (pin "14") (pinfunction "NC_14") (pintype "bidirectional"))
    )
    (net (code "92") (name "unconnected-(U$5-P0B-Pad13)") (class "Default")
      (node (ref "U$5") (pin "13") (pinfunction "P0B_13") (pintype "bidirectional"))
    )
    (net (code "93") (name "unconnected-(U$5-P1B-Pad8)") (class "Default")
      (node (ref "U$5") (pin "8") (pinfunction "P1B_8") (pintype "bidirectional"))
    )
    (net (code "94") (name "unconnected-(U$5-P2B-Pad18)") (class "Default")
      (node (ref "U$5") (pin "18") (pinfunction "P2B_18") (pintype "bidirectional"))
    )
    (net (code "95") (name "unconnected-(U$5-P3B-Pad3)") (class "Default")
      (node (ref "U$5") (pin "3") (pinfunction "P3B_3") (pintype "bidirectional"))
    )
    (net (code "96") (name "unconnected-(U$9-5V_MIDIIN_NC-Pad15)") (class "Default")
      (node (ref "U$9") (pin "15") (pinfunction "5V_MIDIIN_NC_15") (pintype "bidirectional"))
    )
    (net (code "97") (name "unconnected-(U$9-GND_MIDIOUT-Pad12)") (class "Default")
      (node (ref "U$9") (pin "12") (pinfunction "GND_MIDIOUT_12") (pintype "bidirectional"))
    )
  )
)
